# design.net
KiCad netlist of a schematic drawn in Altium Designer
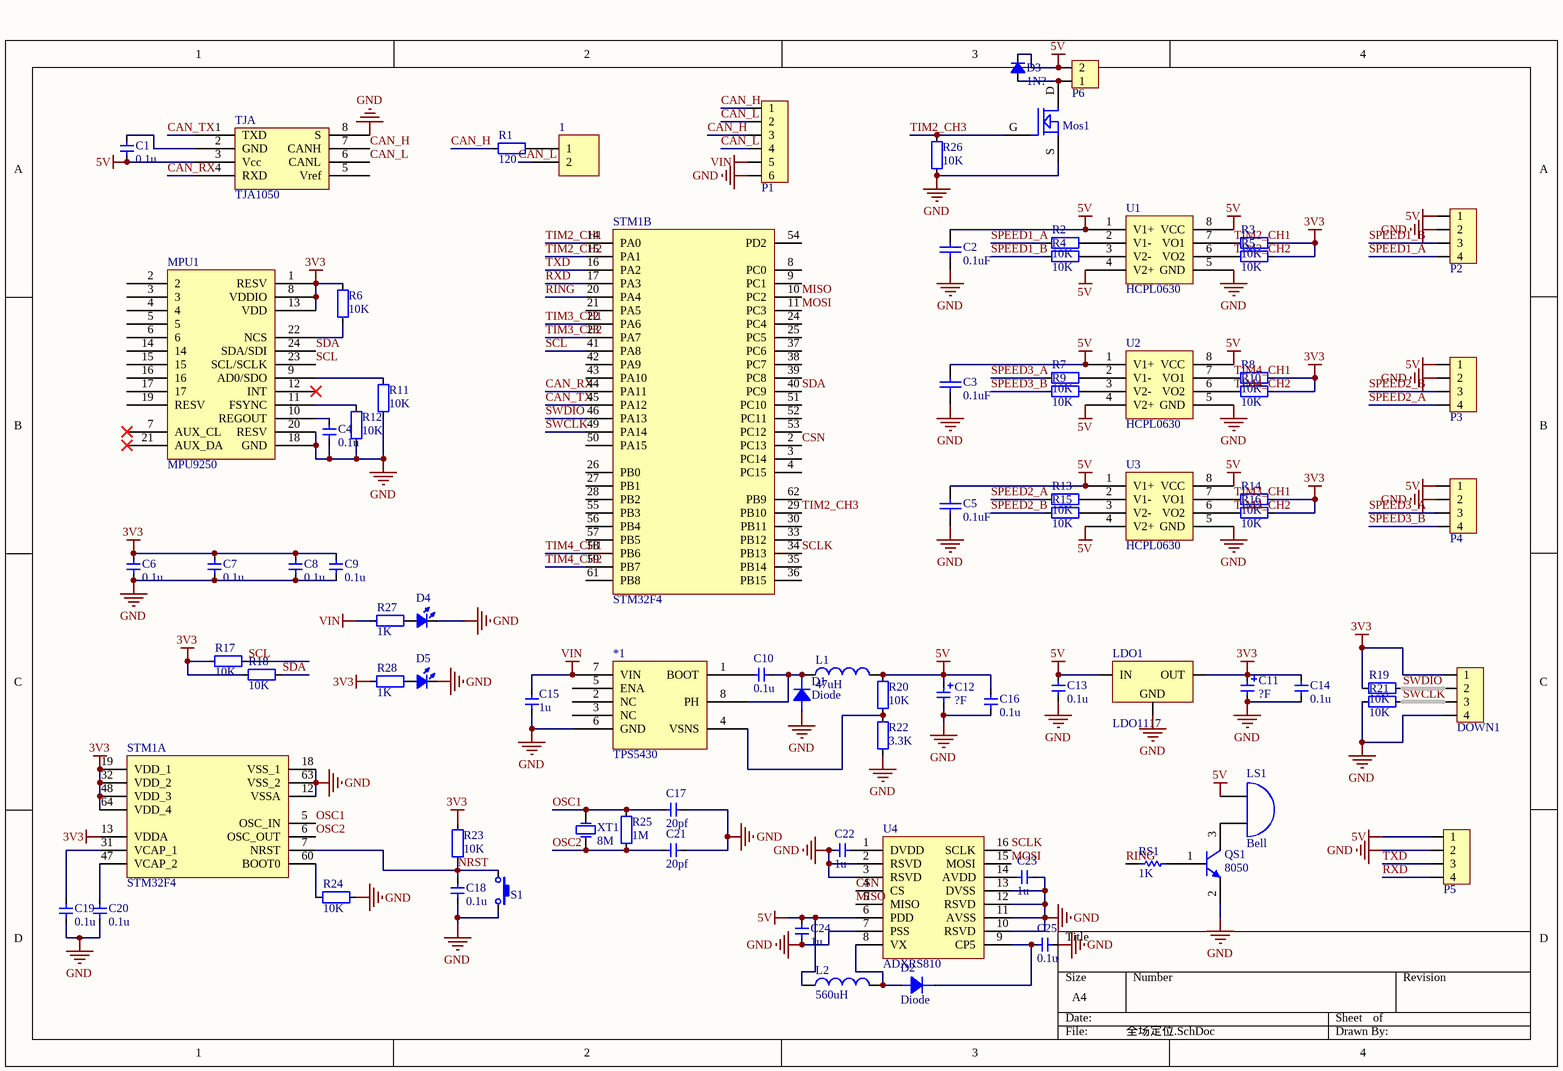
[diagram p0: 全场定位.SchDoc]

(export (version "E")
  (design (tool "Eeschema 10.0.6"))
  (components
    (comp (ref "*1")
      (value "TPS5430")
      (footprint "SOP_E150_8")
      (libsource (lib "SCH_IntegratedCircuit") (part "TPS5430"))
    )
    (comp (ref "1")
      (value "Header 2")
      (footprint "SIP2")
      (description "Header, 2-Pin")
      (fields (field (name "PUBLISHER") "Altium Limited"))
      (libsource (lib "Libraries_2014_0618") (part "Header 2"))
    )
    (comp (ref "C1")
      (value "0.1u")
      (footprint "PCB_PassiveCap:CAP_0603")
      (description "Capacitor")
      (fields (field (name "Comment") "Cap_0603"))
      (libsource (lib "SCH_Passive") (part "Cap_0603"))
    )
    (comp (ref "C2")
      (value "0.1uF")
      (footprint "CAP-MLCC-0603")
      (description "Capacitor")
      (fields (field (name "Comment") "Cap") (field (name "PUBLISHER") "Altium Limited"))
      (libsource (lib "K60-mainboard-v3.1") (part "Cap"))
    )
    (comp (ref "C3")
      (value "0.1uF")
      (footprint "CAP-MLCC-0603")
      (description "Capacitor")
      (fields (field (name "Comment") "Cap") (field (name "PUBLISHER") "Altium Limited"))
      (libsource (lib "K60-mainboard-v3.1") (part "Cap"))
    )
    (comp (ref "C4")
      (value "0.1u")
      (footprint "PCB_PassiveCap:CAP_0603")
      (description "Capacitor")
      (fields (field (name "Comment") "Cap_0603"))
      (libsource (lib "SCH_Passive") (part "Cap_0603"))
    )
    (comp (ref "C5")
      (value "0.1uF")
      (footprint "CAP-MLCC-0603")
      (description "Capacitor")
      (fields (field (name "Comment") "Cap") (field (name "PUBLISHER") "Altium Limited"))
      (libsource (lib "K60-mainboard-v3.1") (part "Cap"))
    )
    (comp (ref "C6")
      (value "0.1u")
      (footprint "PCB_PassiveCap:CAP_0603")
      (description "Capacitor")
      (fields (field (name "Comment") "Cap_0603"))
      (libsource (lib "SCH_Passive") (part "Cap_0603"))
    )
    (comp (ref "C7")
      (value "0.1u")
      (footprint "PCB_PassiveCap:CAP_0603")
      (description "Capacitor")
      (fields (field (name "Comment") "Cap_0603"))
      (libsource (lib "SCH_Passive") (part "Cap_0603"))
    )
    (comp (ref "C8")
      (value "0.1u")
      (footprint "PCB_PassiveCap:CAP_0603")
      (description "Capacitor")
      (fields (field (name "Comment") "Cap_0603"))
      (libsource (lib "SCH_Passive") (part "Cap_0603"))
    )
    (comp (ref "C9")
      (value "0.1u")
      (footprint "PCB_PassiveCap:CAP_0603")
      (description "Capacitor")
      (fields (field (name "Comment") "Cap_0603"))
      (libsource (lib "SCH_Passive") (part "Cap_0603"))
    )
    (comp (ref "C10")
      (value "0.1u")
      (footprint "PCB_PassiveCap:CAP_0603")
      (description "Capacitor")
      (fields (field (name "Comment") "Cap_0603"))
      (libsource (lib "SCH_Passive") (part "Cap_0603"))
    )
    (comp (ref "C11")
      (value "?F")
      (footprint "PCB_PassiveCap:CAP_TAN_A1206")
      (description "Capacitor")
      (fields (field (name "Comment") "Cap_Tan_1206"))
      (libsource (lib "SCH_Passive") (part "Cap_Tan_1206"))
    )
    (comp (ref "C12")
      (value "?F")
      (footprint "PCB_PassiveCap:CAP_TAN_A1206")
      (description "Capacitor")
      (fields (field (name "Comment") "Cap_Tan_1206"))
      (libsource (lib "SCH_Passive") (part "Cap_Tan_1206"))
    )
    (comp (ref "C13")
      (value "0.1u")
      (footprint "PCB_PassiveCap:CAP_0603")
      (description "Capacitor")
      (fields (field (name "Comment") "Cap_0603"))
      (libsource (lib "SCH_Passive") (part "Cap_0603"))
    )
    (comp (ref "C14")
      (value "0.1u")
      (footprint "PCB_PassiveCap:CAP_0603")
      (description "Capacitor")
      (fields (field (name "Comment") "Cap_0603"))
      (libsource (lib "SCH_Passive") (part "Cap_0603"))
    )
    (comp (ref "C15")
      (value "1u")
      (footprint "PCB_PassiveCap:CAP_0603")
      (description "Capacitor")
      (fields (field (name "Comment") "Cap_0603"))
      (libsource (lib "SCH_Passive") (part "Cap_0603"))
    )
    (comp (ref "C16")
      (value "0.1u")
      (footprint "PCB_PassiveCap:CAP_0603")
      (description "Capacitor")
      (fields (field (name "Comment") "Cap_0603"))
      (libsource (lib "SCH_Passive") (part "Cap_0603"))
    )
    (comp (ref "C17")
      (value "20pf")
      (footprint "PCB_PassiveCap:CAP_0603")
      (description "Capacitor")
      (fields (field (name "Comment") "Cap_0603"))
      (libsource (lib "SCH_Passive") (part "Cap_0603"))
    )
    (comp (ref "C18")
      (value "0.1u")
      (footprint "PCB_PassiveCap:CAP_0603")
      (description "Capacitor")
      (fields (field (name "Comment") "Cap_0603"))
      (libsource (lib "SCH_Passive") (part "Cap_0603"))
    )
    (comp (ref "C19")
      (value "0.1u")
      (footprint "PCB_PassiveCap:CAP_0603")
      (description "Capacitor")
      (fields (field (name "Comment") "Cap_0603"))
      (libsource (lib "SCH_Passive") (part "Cap_0603"))
    )
    (comp (ref "C20")
      (value "0.1u")
      (footprint "PCB_PassiveCap:CAP_0603")
      (description "Capacitor")
      (fields (field (name "Comment") "Cap_0603"))
      (libsource (lib "SCH_Passive") (part "Cap_0603"))
    )
    (comp (ref "C21")
      (value "20pf")
      (footprint "PCB_PassiveCap:CAP_0603")
      (description "Capacitor")
      (fields (field (name "Comment") "Cap_0603"))
      (libsource (lib "SCH_Passive") (part "Cap_0603"))
    )
    (comp (ref "C22")
      (value "1u")
      (footprint "PCB_PassiveCap:CAP_0603")
      (description "Capacitor")
      (fields (field (name "Comment") "Cap_0603"))
      (libsource (lib "SCH_Passive") (part "Cap_0603"))
    )
    (comp (ref "C23")
      (value "1u")
      (footprint "PCB_PassiveCap:CAP_0603")
      (description "Capacitor")
      (fields (field (name "Comment") "Cap_0603"))
      (libsource (lib "SCH_Passive") (part "Cap_0603"))
    )
    (comp (ref "C24")
      (value "1u")
      (footprint "PCB_PassiveCap:CAP_0603")
      (description "Capacitor")
      (fields (field (name "Comment") "Cap_0603"))
      (libsource (lib "SCH_Passive") (part "Cap_0603"))
    )
    (comp (ref "C25")
      (value "0.1u")
      (footprint "PCB_PassiveCap:CAP_0603")
      (description "Capacitor")
      (fields (field (name "Comment") "Cap_0603"))
      (libsource (lib "SCH_Passive") (part "Cap_0603"))
    )
    (comp (ref "D1") (value "Diode") (footprint "SS34") (libsource (lib "K60-mainboard-v3.1") (part "Diode")))
    (comp (ref "D2") (value "Diode") (footprint "SS34") (libsource (lib "K60-mainboard-v3.1") (part "Diode")))
    (comp (ref "D3")
      (value "1N?")
      (footprint "PCB_ActiveDIO:DO-214AC")
      (description "Diode")
      (fields (field (name "Comment") "Diode_SMA"))
      (libsource (lib "SCH_Active") (part "Diode_SMA"))
    )
    (comp (ref "D4")
      (value "LED_0805")
      (footprint "PCB_ActiveLED:LED_0805_YELLOW")
      (description "LED")
      (libsource (lib "SCH_Active") (part "LED_0805"))
    )
    (comp (ref "D5")
      (value "LED_0805")
      (footprint "PCB_ActiveLED:LED_0805_YELLOW")
      (description "LED")
      (libsource (lib "SCH_Active") (part "LED_0805"))
    )
    (comp (ref "DOWN1")
      (value "HDR1x4_2.54")
      (footprint "PCB_ConnectorHDR:HDR1X4_2.54_180")
      (description "Header")
      (libsource (lib "SCH_ConnectorHDR") (part "HDR1x4_2.54"))
    )
    (comp (ref "L1")
      (value "47uH")
      (footprint "CD74")
      (description "Inductor")
      (fields (field (name "PUBLISHER") "Altium Limited"))
      (libsource (lib "smartcar_example") (part "Inductor"))
    )
    (comp (ref "L2")
      (value "560uH")
      (footprint "CD74")
      (description "Inductor")
      (fields (field (name "PUBLISHER") "Altium Limited"))
      (libsource (lib "smartcar_example") (part "Inductor"))
    )
    (comp (ref "LDO1")
      (value "LDO1117")
      (footprint "PCB_IntegratedCircuit:SOT223-3")
      (description "Power")
      (libsource (lib "SCH_IntegratedCircuit") (part "LDO1117"))
    )
    (comp (ref "LS1")
      (value "Bell")
      (footprint "Ring")
      (description "Electrical Bell")
      (fields (field (name "PUBLISHER") "Altium Limited"))
      (libsource (lib "附加元件") (part "Bell"))
    )
    (comp (ref "Mos1")
      (value "MOSFET N")
      (footprint "Nmos_SOT23")
      (description "MOS SOT23")
      (libsource (lib "SCH_Active") (part "MOSFET N"))
    )
    (comp (ref "MPU1")
      (value "MPU9250")
      (footprint "QFN_P0.4_24")
      (libsource (lib "K60-mainboard-v3.1") (part "MPU9250"))
    )
    (comp (ref "P1")
      (value "HDR1x6_2.54")
      (footprint "green_6p")
      (description "Header")
      (libsource (lib "SCH_ConnectorHDR") (part "HDR1x6_2.54"))
    )
    (comp (ref "P2")
      (value "HDR1x4_2.54")
      (footprint "Libraries_2014_0618:Green_4P")
      (description "Header")
      (libsource (lib "SCH_ConnectorHDR") (part "HDR1x4_2.54"))
    )
    (comp (ref "P3")
      (value "HDR1x4_2.54")
      (footprint "green_4p")
      (description "Header")
      (libsource (lib "SCH_ConnectorHDR") (part "HDR1x4_2.54"))
    )
    (comp (ref "P4")
      (value "HDR1x4_2.54")
      (footprint "green_4p")
      (description "Header")
      (libsource (lib "SCH_ConnectorHDR") (part "HDR1x4_2.54"))
    )
    (comp (ref "P5")
      (value "HDR1x4_2.54")
      (footprint "PCB_ConnectorHDR:HDR1X4_2.54_180")
      (description "Header")
      (libsource (lib "SCH_ConnectorHDR") (part "HDR1x4_2.54"))
    )
    (comp (ref "P6") (value "Connector") (footprint "Green 2P") (libsource (lib "SCH_Connector") (part "2P")))
    (comp (ref "QS1")
      (value "8050")
      (footprint "SOT-23B_N")
      (description "NPN Bipolar Transistor")
      (fields (field (name "PUBLISHER") "Altium Limited"))
      (libsource (lib "附加元件") (part "QNPN"))
    )
    (comp (ref "R1")
      (value "120")
      (footprint "PCB_PassiveRes:RES_0603")
      (description "Resistor")
      (fields (field (name "Comment") "Res_0603"))
      (libsource (lib "SCH_Passive") (part "Res_0603"))
    )
    (comp (ref "R2")
      (value "10K")
      (footprint "PCB_PassiveRes:RES_0603")
      (description "Resistor")
      (fields (field (name "Comment") "Res_0603"))
      (libsource (lib "") (part "Res_0603_2"))
    )
    (comp (ref "R3")
      (value "10K")
      (footprint "PCB_PassiveRes:RES_0603")
      (description "Resistor")
      (fields (field (name "Comment") "Res_0603"))
      (libsource (lib "") (part "Res_0603_2"))
    )
    (comp (ref "R4")
      (value "10K")
      (footprint "PCB_PassiveRes:RES_0603")
      (description "Resistor")
      (fields (field (name "Comment") "Res_0603"))
      (libsource (lib "") (part "Res_0603_2"))
    )
    (comp (ref "R5")
      (value "10K")
      (footprint "PCB_PassiveRes:RES_0603")
      (description "Resistor")
      (fields (field (name "Comment") "Res_0603"))
      (libsource (lib "") (part "Res_0603_2"))
    )
    (comp (ref "R6")
      (value "10K")
      (footprint "PCB_PassiveRes:RES_0603")
      (description "Resistor")
      (fields (field (name "Comment") "Res_0603"))
      (libsource (lib "") (part "Res_0603_1"))
    )
    (comp (ref "R7")
      (value "10K")
      (footprint "PCB_PassiveRes:RES_0603")
      (description "Resistor")
      (fields (field (name "Comment") "Res_0603"))
      (libsource (lib "") (part "Res_0603_2"))
    )
    (comp (ref "R8")
      (value "10K")
      (footprint "PCB_PassiveRes:RES_0603")
      (description "Resistor")
      (fields (field (name "Comment") "Res_0603"))
      (libsource (lib "") (part "Res_0603_2"))
    )
    (comp (ref "R9")
      (value "10K")
      (footprint "PCB_PassiveRes:RES_0603")
      (description "Resistor")
      (fields (field (name "Comment") "Res_0603"))
      (libsource (lib "") (part "Res_0603_2"))
    )
    (comp (ref "R10")
      (value "10K")
      (footprint "PCB_PassiveRes:RES_0603")
      (description "Resistor")
      (fields (field (name "Comment") "Res_0603"))
      (libsource (lib "") (part "Res_0603_2"))
    )
    (comp (ref "R11")
      (value "10K")
      (footprint "PCB_PassiveRes:RES_0603")
      (description "Resistor")
      (fields (field (name "Comment") "Res_0603"))
      (libsource (lib "") (part "Res_0603_1"))
    )
    (comp (ref "R12")
      (value "10K")
      (footprint "PCB_PassiveRes:RES_0603")
      (description "Resistor")
      (fields (field (name "Comment") "Res_0603"))
      (libsource (lib "") (part "Res_0603_1"))
    )
    (comp (ref "R13")
      (value "10K")
      (footprint "PCB_PassiveRes:RES_0603")
      (description "Resistor")
      (fields (field (name "Comment") "Res_0603"))
      (libsource (lib "") (part "Res_0603_2"))
    )
    (comp (ref "R14")
      (value "10K")
      (footprint "PCB_PassiveRes:RES_0603")
      (description "Resistor")
      (fields (field (name "Comment") "Res_0603"))
      (libsource (lib "") (part "Res_0603_2"))
    )
    (comp (ref "R15")
      (value "10K")
      (footprint "PCB_PassiveRes:RES_0603")
      (description "Resistor")
      (fields (field (name "Comment") "Res_0603"))
      (libsource (lib "") (part "Res_0603_2"))
    )
    (comp (ref "R16")
      (value "10K")
      (footprint "PCB_PassiveRes:RES_0603")
      (description "Resistor")
      (fields (field (name "Comment") "Res_0603"))
      (libsource (lib "") (part "Res_0603_2"))
    )
    (comp (ref "R17")
      (value "10K")
      (footprint "PCB_PassiveRes:RES_0603")
      (description "Resistor")
      (fields (field (name "Comment") "Res_0603"))
      (libsource (lib "") (part "Res_0603_2"))
    )
    (comp (ref "R18")
      (value "10K")
      (footprint "PCB_PassiveRes:RES_0603")
      (description "Resistor")
      (fields (field (name "Comment") "Res_0603"))
      (libsource (lib "") (part "Res_0603_2"))
    )
    (comp (ref "R19")
      (value "10K")
      (footprint "PCB_PassiveRes:RES_0603")
      (description "Resistor")
      (fields (field (name "Comment") "Res_0603"))
      (libsource (lib "") (part "Res_0603_2"))
    )
    (comp (ref "R20")
      (value "10K")
      (footprint "PCB_PassiveRes:RES_0603")
      (description "Resistor")
      (fields (field (name "Comment") "Res_0603"))
      (libsource (lib "") (part "Res_0603_1"))
    )
    (comp (ref "R21")
      (value "10K")
      (footprint "PCB_PassiveRes:RES_0603")
      (description "Resistor")
      (fields (field (name "Comment") "Res_0603"))
      (libsource (lib "") (part "Res_0603_2"))
    )
    (comp (ref "R22")
      (value "3.3K")
      (footprint "PCB_PassiveRes:RES_0603")
      (description "Resistor")
      (fields (field (name "Comment") "Res_0603"))
      (libsource (lib "") (part "Res_0603_1"))
    )
    (comp (ref "R23")
      (value "10K")
      (footprint "PCB_PassiveRes:RES_0603")
      (description "Resistor")
      (fields (field (name "Comment") "Res_0603"))
      (libsource (lib "") (part "Res_0603_1"))
    )
    (comp (ref "R24")
      (value "10K")
      (footprint "PCB_PassiveRes:RES_0603")
      (description "Resistor")
      (fields (field (name "Comment") "Res_0603"))
      (libsource (lib "SCH_Passive") (part "Res_0603"))
    )
    (comp (ref "R25")
      (value "1M")
      (footprint "PCB_PassiveRes:RES_0603")
      (description "Resistor")
      (fields (field (name "Comment") "Res_0603"))
      (libsource (lib "") (part "Res_0603_3"))
    )
    (comp (ref "R26")
      (value "10K")
      (footprint "PCB_PassiveRes:RES_0603")
      (description "Resistor")
      (fields (field (name "Comment") "Res_0603"))
      (libsource (lib "") (part "Res_0603_1"))
    )
    (comp (ref "R27")
      (value "1K")
      (footprint "PCB_PassiveRes:RES_0603")
      (description "Resistor")
      (fields (field (name "Comment") "Res_0603"))
      (libsource (lib "SCH_Passive") (part "Res_0603"))
    )
    (comp (ref "R28")
      (value "1K")
      (footprint "PCB_PassiveRes:RES_0603")
      (description "Resistor")
      (fields (field (name "Comment") "Res_0603"))
      (libsource (lib "SCH_Passive") (part "Res_0603"))
    )
    (comp (ref "RS1")
      (value "1K")
      (footprint "RES-0603")
      (description "Resistor")
      (fields (field (name "Comment") "Res1") (field (name "PUBLISHER") "Altium Limited"))
      (libsource (lib "K60-mainboard-v3.1") (part "Res1"))
    )
    (comp (ref "S1")
      (value "ButtonTACT_3x4x2_180")
      (footprint "PCB_Switch:ButtonTACT_3x4x2_180H")
      (description "Button")
      (libsource (lib "SCH_Switch") (part "ButtonTACT_3x4x2_180"))
    )
    (comp (ref "STM1")
      (value "STM32F4")
      (footprint "PCB_IntegratedCircuit:LQFP_P0.5_64")
      (description "MCU")
      (libsource (lib "SCH_IntegratedCircuit") (part "STM32F405R"))
    )
    (comp (ref "TJA")
      (value "TJA1050")
      (footprint "SOP_E150_8")
      (libsource (lib "SCH_IntegratedCircuit") (part "TJA1050"))
    )
    (comp (ref "U1")
      (value "HCPL0630")
      (footprint "SOP_E150_8")
      (libsource (lib "SCH_IntegratedCircuit") (part "HCPL0630"))
    )
    (comp (ref "U2")
      (value "HCPL0630")
      (footprint "SOP_E150_8")
      (libsource (lib "SCH_IntegratedCircuit") (part "HCPL0630"))
    )
    (comp (ref "U3")
      (value "HCPL0630")
      (footprint "SOP_E150_8")
      (libsource (lib "SCH_IntegratedCircuit") (part "HCPL0630"))
    )
    (comp (ref "U4")
      (value "ADXRS810")
      (footprint "sop16")
      (libsource (lib "SCH_IntegratedCircuit") (part "ADXRS810"))
    )
    (comp (ref "XT1")
      (value "8M")
      (footprint "PCB_Oscillator:XT_5032_2")
      (description "Crystal Oscillator")
      (fields (field (name "Comment") "XTAL_5032_2P"))
      (libsource (lib "SCH_Oscillator") (part "XTAL_5032_2P"))
    )
  )
  (nets
    (net (code "1") (name "/CAN_H") (class "Default")
      (node (ref "P1") (pin "1") (pinfunction "1_1") (pintype "passive"))
      (node (ref "P1") (pin "3") (pinfunction "3_3") (pintype "passive"))
      (node (ref "R1") (pin "1") (pinfunction "1_1") (pintype "passive"))
      (node (ref "TJA") (pin "7") (pinfunction "CANH_7") (pintype "passive"))
    )
    (net (code "2") (name "/CAN_L") (class "Default")
      (node (ref "1") (pin "2") (pinfunction "2_2") (pintype "passive"))
      (node (ref "P1") (pin "2") (pinfunction "2_2") (pintype "passive"))
      (node (ref "P1") (pin "4") (pinfunction "4_4") (pintype "passive"))
      (node (ref "TJA") (pin "6") (pinfunction "CANL_6") (pintype "passive"))
    )
    (net (code "3") (name "/CAN_RX") (class "Default")
      (node (ref "STM1") (pin "44") (pinfunction "PA11_44") (pintype "passive"))
      (node (ref "TJA") (pin "4") (pinfunction "RXD_4") (pintype "passive"))
    )
    (net (code "4") (name "/CAN_TX") (class "Default")
      (node (ref "STM1") (pin "45") (pinfunction "PA12_45") (pintype "passive"))
      (node (ref "TJA") (pin "1") (pinfunction "TXD_1") (pintype "passive"))
    )
    (net (code "5") (name "/CSN") (class "Default")
      (node (ref "STM1") (pin "2") (pinfunction "PC13_2") (pintype "passive"))
      (node (ref "U4") (pin "4") (pinfunction "CS_4") (pintype "passive"))
    )
    (net (code "6") (name "/MISO") (class "Default")
      (node (ref "STM1") (pin "10") (pinfunction "PC2_10") (pintype "passive"))
      (node (ref "U4") (pin "5") (pinfunction "MISO_5") (pintype "passive"))
    )
    (net (code "7") (name "/MOSI") (class "Default")
      (node (ref "STM1") (pin "11") (pinfunction "PC3_11") (pintype "passive"))
      (node (ref "U4") (pin "15") (pinfunction "MOSI_15") (pintype "passive"))
    )
    (net (code "8") (name "/NRST") (class "Default")
      (node (ref "C18") (pin "2") (pinfunction "2_2") (pintype "passive"))
      (node (ref "R23") (pin "2") (pinfunction "2_2") (pintype "passive"))
      (node (ref "S1") (pin "1") (pinfunction "1_1") (pintype "passive"))
      (node (ref "STM1") (pin "7") (pinfunction "NRST_7") (pintype "passive"))
    )
    (net (code "9") (name "/OSC1") (class "Default")
      (node (ref "C17") (pin "2") (pinfunction "2_2") (pintype "passive"))
      (node (ref "R25") (pin "2") (pinfunction "2_2") (pintype "passive"))
      (node (ref "STM1") (pin "5") (pinfunction "OSC_IN_5") (pintype "passive"))
      (node (ref "XT1") (pin "2") (pinfunction "OSC2_2") (pintype "passive"))
    )
    (net (code "10") (name "/OSC2") (class "Default")
      (node (ref "C21") (pin "2") (pinfunction "2_2") (pintype "passive"))
      (node (ref "R25") (pin "1") (pinfunction "1_1") (pintype "passive"))
      (node (ref "STM1") (pin "6") (pinfunction "OSC_OUT_6") (pintype "passive"))
      (node (ref "XT1") (pin "1") (pinfunction "OSC1_1") (pintype "passive"))
    )
    (net (code "11") (name "/RING") (class "Default")
      (node (ref "RS1") (pin "2") (pinfunction "2_2") (pintype "passive"))
      (node (ref "STM1") (pin "20") (pinfunction "PA4_20") (pintype "passive"))
    )
    (net (code "12") (name "/RXD") (class "Default")
      (node (ref "P5") (pin "4") (pinfunction "4_4") (pintype "passive"))
      (node (ref "STM1") (pin "17") (pinfunction "PA3_17") (pintype "passive"))
    )
    (net (code "13") (name "/SCL") (class "Default")
      (node (ref "MPU1") (pin "23") (pinfunction "SCL/SCLK_23") (pintype "passive"))
      (node (ref "R17") (pin "1") (pinfunction "1_1") (pintype "passive"))
      (node (ref "STM1") (pin "41") (pinfunction "PA8_41") (pintype "passive"))
    )
    (net (code "14") (name "/SCLK") (class "Default")
      (node (ref "STM1") (pin "34") (pinfunction "PB13_34") (pintype "passive"))
      (node (ref "U4") (pin "16") (pinfunction "SCLK_16") (pintype "passive"))
    )
    (net (code "15") (name "/SDA") (class "Default")
      (node (ref "MPU1") (pin "24") (pinfunction "SDA/SDI_24") (pintype "passive"))
      (node (ref "R18") (pin "1") (pinfunction "1_1") (pintype "passive"))
      (node (ref "STM1") (pin "40") (pinfunction "PC9_40") (pintype "passive"))
    )
    (net (code "16") (name "/SPEED1_A") (class "Default")
      (node (ref "P2") (pin "4") (pinfunction "4_4") (pintype "passive"))
      (node (ref "R2") (pin "2") (pinfunction "2_2") (pintype "passive"))
    )
    (net (code "17") (name "/SPEED1_B") (class "Default")
      (node (ref "P2") (pin "3") (pinfunction "3_3") (pintype "passive"))
      (node (ref "R4") (pin "2") (pinfunction "2_2") (pintype "passive"))
    )
    (net (code "18") (name "/SPEED2_A") (class "Default")
      (node (ref "P3") (pin "4") (pinfunction "4_4") (pintype "passive"))
      (node (ref "R13") (pin "2") (pinfunction "2_2") (pintype "passive"))
    )
    (net (code "19") (name "/SPEED2_B") (class "Default")
      (node (ref "P3") (pin "3") (pinfunction "3_3") (pintype "passive"))
      (node (ref "R15") (pin "2") (pinfunction "2_2") (pintype "passive"))
    )
    (net (code "20") (name "/SPEED3_A") (class "Default")
      (node (ref "P4") (pin "3") (pinfunction "3_3") (pintype "passive"))
      (node (ref "R7") (pin "2") (pinfunction "2_2") (pintype "passive"))
    )
    (net (code "21") (name "/SPEED3_B") (class "Default")
      (node (ref "P4") (pin "4") (pinfunction "4_4") (pintype "passive"))
      (node (ref "R9") (pin "2") (pinfunction "2_2") (pintype "passive"))
    )
    (net (code "22") (name "/SWCLK") (class "Default")
      (node (ref "DOWN1") (pin "3") (pinfunction "3_3") (pintype "passive"))
      (node (ref "R21") (pin "1") (pinfunction "1_1") (pintype "passive"))
      (node (ref "STM1") (pin "49") (pinfunction "PA14_49") (pintype "passive"))
    )
    (net (code "23") (name "/SWDIO") (class "Default")
      (node (ref "DOWN1") (pin "2") (pinfunction "2_2") (pintype "passive"))
      (node (ref "R19") (pin "1") (pinfunction "1_1") (pintype "passive"))
      (node (ref "STM1") (pin "46") (pinfunction "PA13_46") (pintype "passive"))
    )
    (net (code "24") (name "/TIM2_CH1") (class "Default")
      (node (ref "R3") (pin "2") (pinfunction "2_2") (pintype "passive"))
      (node (ref "STM1") (pin "14") (pinfunction "PA0_14") (pintype "passive"))
      (node (ref "U1") (pin "7") (pinfunction "VO1_7") (pintype "passive"))
    )
    (net (code "25") (name "/TIM2_CH2") (class "Default")
      (node (ref "R5") (pin "2") (pinfunction "2_2") (pintype "passive"))
      (node (ref "STM1") (pin "15") (pinfunction "PA1_15") (pintype "passive"))
      (node (ref "U1") (pin "6") (pinfunction "VO2_6") (pintype "passive"))
    )
    (net (code "26") (name "/TIM2_CH3") (class "Default")
      (node (ref "Mos1") (pin "G") (pinfunction "G_G") (pintype "passive"))
      (node (ref "R26") (pin "1") (pinfunction "1_1") (pintype "passive"))
      (node (ref "STM1") (pin "29") (pinfunction "PB10_29") (pintype "passive"))
    )
    (net (code "27") (name "/TIM3_CH1") (class "Default")
      (node (ref "R14") (pin "2") (pinfunction "2_2") (pintype "passive"))
      (node (ref "STM1") (pin "22") (pinfunction "PA6_22") (pintype "passive"))
      (node (ref "U3") (pin "7") (pinfunction "VO1_7") (pintype "passive"))
    )
    (net (code "28") (name "/TIM3_CH2") (class "Default")
      (node (ref "R16") (pin "2") (pinfunction "2_2") (pintype "passive"))
      (node (ref "STM1") (pin "23") (pinfunction "PA7_23") (pintype "passive"))
      (node (ref "U3") (pin "6") (pinfunction "VO2_6") (pintype "passive"))
    )
    (net (code "29") (name "/TIM4_CH1") (class "Default")
      (node (ref "R8") (pin "2") (pinfunction "2_2") (pintype "passive"))
      (node (ref "STM1") (pin "58") (pinfunction "PB6_58") (pintype "passive"))
      (node (ref "U2") (pin "7") (pinfunction "VO1_7") (pintype "passive"))
    )
    (net (code "30") (name "/TIM4_CH2") (class "Default")
      (node (ref "R10") (pin "2") (pinfunction "2_2") (pintype "passive"))
      (node (ref "STM1") (pin "59") (pinfunction "PB7_59") (pintype "passive"))
      (node (ref "U2") (pin "6") (pinfunction "VO2_6") (pintype "passive"))
    )
    (net (code "31") (name "/TXD") (class "Default")
      (node (ref "P5") (pin "3") (pinfunction "3_3") (pintype "passive"))
      (node (ref "STM1") (pin "16") (pinfunction "PA2_16") (pintype "passive"))
    )
    (net (code "32") (name "3V3") (class "Default")
      (node (ref "C11") (pin "1") (pinfunction "1_1") (pintype "passive"))
      (node (ref "C14") (pin "1") (pinfunction "1_1") (pintype "passive"))
      (node (ref "C6") (pin "2") (pinfunction "2_2") (pintype "passive"))
      (node (ref "C7") (pin "2") (pinfunction "2_2") (pintype "passive"))
      (node (ref "C8") (pin "2") (pinfunction "2_2") (pintype "passive"))
      (node (ref "C9") (pin "2") (pinfunction "2_2") (pintype "passive"))
      (node (ref "DOWN1") (pin "1") (pinfunction "1_1") (pintype "passive"))
      (node (ref "LDO1") (pin "2") (pinfunction "OUT_2") (pintype "power_in"))
      (node (ref "MPU1") (pin "1") (pinfunction "RESV_1") (pintype "passive"))
      (node (ref "MPU1") (pin "13") (pinfunction "VDD_13") (pintype "passive"))
      (node (ref "MPU1") (pin "8") (pinfunction "VDDIO_8") (pintype "passive"))
      (node (ref "R10") (pin "1") (pinfunction "1_1") (pintype "passive"))
      (node (ref "R14") (pin "1") (pinfunction "1_1") (pintype "passive"))
      (node (ref "R16") (pin "1") (pinfunction "1_1") (pintype "passive"))
      (node (ref "R17") (pin "2") (pinfunction "2_2") (pintype "passive"))
      (node (ref "R18") (pin "2") (pinfunction "2_2") (pintype "passive"))
      (node (ref "R19") (pin "2") (pinfunction "2_2") (pintype "passive"))
      (node (ref "R23") (pin "1") (pinfunction "1_1") (pintype "passive"))
      (node (ref "R28") (pin "1") (pinfunction "1_1") (pintype "passive"))
      (node (ref "R3") (pin "1") (pinfunction "1_1") (pintype "passive"))
      (node (ref "R5") (pin "1") (pinfunction "1_1") (pintype "passive"))
      (node (ref "R6") (pin "1") (pinfunction "1_1") (pintype "passive"))
      (node (ref "R8") (pin "1") (pinfunction "1_1") (pintype "passive"))
      (node (ref "STM1") (pin "13") (pinfunction "VDDA_13") (pintype "passive"))
      (node (ref "STM1") (pin "19") (pinfunction "VDD_1_19") (pintype "passive"))
      (node (ref "STM1") (pin "32") (pinfunction "VDD_2_32") (pintype "passive"))
      (node (ref "STM1") (pin "48") (pinfunction "VDD_3_48") (pintype "passive"))
      (node (ref "STM1") (pin "64") (pinfunction "VDD_4_64") (pintype "passive"))
    )
    (net (code "33") (name "5V") (class "Default")
      (node (ref "C1") (pin "1") (pinfunction "1_1") (pintype "passive"))
      (node (ref "C12") (pin "1") (pinfunction "1_1") (pintype "passive"))
      (node (ref "C13") (pin "1") (pinfunction "1_1") (pintype "passive"))
      (node (ref "C16") (pin "1") (pinfunction "1_1") (pintype "passive"))
      (node (ref "C2") (pin "1") (pinfunction "1_1") (pintype "passive"))
      (node (ref "C24") (pin "1") (pinfunction "1_1") (pintype "passive"))
      (node (ref "C3") (pin "1") (pinfunction "1_1") (pintype "passive"))
      (node (ref "C5") (pin "1") (pinfunction "1_1") (pintype "passive"))
      (node (ref "D3") (pin "2") (pinfunction "K_2") (pintype "passive"))
      (node (ref "L1") (pin "2") (pinfunction "2_2") (pintype "passive"))
      (node (ref "L2") (pin "1") (pinfunction "1_1") (pintype "passive"))
      (node (ref "LDO1") (pin "3") (pinfunction "IN_3") (pintype "power_in"))
      (node (ref "LS1") (pin "1") (pinfunction "A_1") (pintype "passive"))
      (node (ref "P2") (pin "1") (pinfunction "1_1") (pintype "passive"))
      (node (ref "P3") (pin "1") (pinfunction "1_1") (pintype "passive"))
      (node (ref "P4") (pin "1") (pinfunction "1_1") (pintype "passive"))
      (node (ref "P5") (pin "1") (pinfunction "1_1") (pintype "passive"))
      (node (ref "P6") (pin "2") (pinfunction "2_2") (pintype "passive"))
      (node (ref "R20") (pin "1") (pinfunction "1_1") (pintype "passive"))
      (node (ref "TJA") (pin "3") (pinfunction "Vcc_3") (pintype "passive"))
      (node (ref "U1") (pin "1") (pinfunction "V1+_1") (pintype "passive"))
      (node (ref "U1") (pin "4") (pinfunction "V2+_4") (pintype "passive"))
      (node (ref "U1") (pin "8") (pinfunction "VCC_8") (pintype "passive"))
      (node (ref "U2") (pin "1") (pinfunction "V1+_1") (pintype "passive"))
      (node (ref "U2") (pin "4") (pinfunction "V2+_4") (pintype "passive"))
      (node (ref "U2") (pin "8") (pinfunction "VCC_8") (pintype "passive"))
      (node (ref "U3") (pin "1") (pinfunction "V1+_1") (pintype "passive"))
      (node (ref "U3") (pin "4") (pinfunction "V2+_4") (pintype "passive"))
      (node (ref "U3") (pin "8") (pinfunction "VCC_8") (pintype "passive"))
      (node (ref "U4") (pin "6") (pinfunction "PDD_6") (pintype "passive"))
    )
    (net (code "34") (name "GND") (class "Default")
      (node (ref "*1") (pin "6") (pinfunction "GND_6") (pintype "passive"))
      (node (ref "C11") (pin "2") (pinfunction "2_2") (pintype "passive"))
      (node (ref "C12") (pin "2") (pinfunction "2_2") (pintype "passive"))
      (node (ref "C13") (pin "2") (pinfunction "2_2") (pintype "passive"))
      (node (ref "C14") (pin "2") (pinfunction "2_2") (pintype "passive"))
      (node (ref "C15") (pin "1") (pinfunction "1_1") (pintype "passive"))
      (node (ref "C16") (pin "2") (pinfunction "2_2") (pintype "passive"))
      (node (ref "C17") (pin "1") (pinfunction "1_1") (pintype "passive"))
      (node (ref "C18") (pin "1") (pinfunction "1_1") (pintype "passive"))
      (node (ref "C19") (pin "2") (pinfunction "2_2") (pintype "passive"))
      (node (ref "C2") (pin "2") (pinfunction "2_2") (pintype "passive"))
      (node (ref "C20") (pin "2") (pinfunction "2_2") (pintype "passive"))
      (node (ref "C21") (pin "1") (pinfunction "1_1") (pintype "passive"))
      (node (ref "C22") (pin "2") (pinfunction "2_2") (pintype "passive"))
      (node (ref "C23") (pin "2") (pinfunction "2_2") (pintype "passive"))
      (node (ref "C24") (pin "2") (pinfunction "2_2") (pintype "passive"))
      (node (ref "C25") (pin "1") (pinfunction "1_1") (pintype "passive"))
      (node (ref "C3") (pin "2") (pinfunction "2_2") (pintype "passive"))
      (node (ref "C4") (pin "2") (pinfunction "2_2") (pintype "passive"))
      (node (ref "C5") (pin "2") (pinfunction "2_2") (pintype "passive"))
      (node (ref "C6") (pin "1") (pinfunction "1_1") (pintype "passive"))
      (node (ref "C7") (pin "1") (pinfunction "1_1") (pintype "passive"))
      (node (ref "C8") (pin "1") (pinfunction "1_1") (pintype "passive"))
      (node (ref "C9") (pin "1") (pinfunction "1_1") (pintype "passive"))
      (node (ref "D1") (pin "A") (pinfunction "1_A") (pintype "passive"))
      (node (ref "D4") (pin "2") (pinfunction "K_2") (pintype "passive"))
      (node (ref "D5") (pin "2") (pinfunction "K_2") (pintype "passive"))
      (node (ref "DOWN1") (pin "4") (pinfunction "4_4") (pintype "passive"))
      (node (ref "LDO1") (pin "1") (pinfunction "GND_1") (pintype "power_in"))
      (node (ref "MPU1") (pin "18") (pinfunction "GND_18") (pintype "passive"))
      (node (ref "MPU1") (pin "20") (pinfunction "RESV_20") (pintype "passive"))
      (node (ref "Mos1") (pin "S") (pinfunction "S_S") (pintype "passive"))
      (node (ref "P1") (pin "6") (pinfunction "6_6") (pintype "passive"))
      (node (ref "P2") (pin "2") (pinfunction "2_2") (pintype "passive"))
      (node (ref "P3") (pin "2") (pinfunction "2_2") (pintype "passive"))
      (node (ref "P4") (pin "2") (pinfunction "2_2") (pintype "passive"))
      (node (ref "P5") (pin "2") (pinfunction "2_2") (pintype "passive"))
      (node (ref "QS1") (pin "2") (pinfunction "E_2") (pintype "passive"))
      (node (ref "R11") (pin "2") (pinfunction "2_2") (pintype "passive"))
      (node (ref "R12") (pin "2") (pinfunction "2_2") (pintype "passive"))
      (node (ref "R21") (pin "2") (pinfunction "2_2") (pintype "passive"))
      (node (ref "R22") (pin "2") (pinfunction "2_2") (pintype "passive"))
      (node (ref "R24") (pin "2") (pinfunction "2_2") (pintype "passive"))
      (node (ref "R26") (pin "2") (pinfunction "2_2") (pintype "passive"))
      (node (ref "S1") (pin "2") (pinfunction "2_2") (pintype "passive"))
      (node (ref "STM1") (pin "12") (pinfunction "VSSA_12") (pintype "passive"))
      (node (ref "STM1") (pin "18") (pinfunction "VSS_1_18") (pintype "passive"))
      (node (ref "STM1") (pin "63") (pinfunction "VSS_2_63") (pintype "passive"))
      (node (ref "TJA") (pin "8") (pinfunction "S_8") (pintype "passive"))
      (node (ref "U1") (pin "5") (pinfunction "GND_5") (pintype "passive"))
      (node (ref "U2") (pin "5") (pinfunction "GND_5") (pintype "passive"))
      (node (ref "U3") (pin "5") (pinfunction "GND_5") (pintype "passive"))
      (node (ref "U4") (pin "10") (pinfunction "RSVD_10") (pintype "passive"))
      (node (ref "U4") (pin "11") (pinfunction "AVSS_11") (pintype "passive"))
      (node (ref "U4") (pin "12") (pinfunction "RSVD_12") (pintype "passive"))
      (node (ref "U4") (pin "13") (pinfunction "DVSS_13") (pintype "passive"))
      (node (ref "U4") (pin "2") (pinfunction "RSVD_2") (pintype "passive"))
      (node (ref "U4") (pin "3") (pinfunction "RSVD_3") (pintype "passive"))
      (node (ref "U4") (pin "7") (pinfunction "PSS_7") (pintype "passive"))
    )
    (net (code "35") (name "Net-(*1-BOOT)") (class "Default")
      (node (ref "*1") (pin "1") (pinfunction "BOOT_1") (pintype "passive"))
      (node (ref "C10") (pin "2") (pinfunction "2_2") (pintype "passive"))
    )
    (net (code "36") (name "Net-(*1-PH)") (class "Default")
      (node (ref "*1") (pin "8") (pinfunction "PH_8") (pintype "passive"))
      (node (ref "C10") (pin "1") (pinfunction "1_1") (pintype "passive"))
      (node (ref "D1") (pin "K") (pinfunction "2_K") (pintype "passive"))
      (node (ref "L1") (pin "1") (pinfunction "1_1") (pintype "passive"))
    )
    (net (code "37") (name "Net-(*1-VSNS)") (class "Default")
      (node (ref "*1") (pin "4") (pinfunction "VSNS_4") (pintype "passive"))
      (node (ref "R20") (pin "2") (pinfunction "2_2") (pintype "passive"))
      (node (ref "R22") (pin "1") (pinfunction "1_1") (pintype "passive"))
    )
    (net (code "38") (name "Net-(1-Pad1)") (class "Default")
      (node (ref "1") (pin "1") (pinfunction "1_1") (pintype "passive"))
      (node (ref "R1") (pin "2") (pinfunction "2_2") (pintype "passive"))
    )
    (net (code "39") (name "Net-(D2-1)") (class "Default")
      (node (ref "D2") (pin "A") (pinfunction "1_A") (pintype "passive"))
      (node (ref "L2") (pin "2") (pinfunction "2_2") (pintype "passive"))
      (node (ref "U4") (pin "8") (pinfunction "VX_8") (pintype "passive"))
    )
    (net (code "40") (name "Net-(D2-2)") (class "Default")
      (node (ref "C25") (pin "2") (pinfunction "2_2") (pintype "passive"))
      (node (ref "D2") (pin "K") (pinfunction "2_K") (pintype "passive"))
      (node (ref "U4") (pin "9") (pinfunction "CP5_9") (pintype "passive"))
    )
    (net (code "41") (name "Net-(D3-A)") (class "Default")
      (node (ref "D3") (pin "1") (pinfunction "A_1") (pintype "passive"))
      (node (ref "Mos1") (pin "D") (pinfunction "D_D") (pintype "passive"))
      (node (ref "P6") (pin "1") (pinfunction "1_1") (pintype "passive"))
    )
    (net (code "42") (name "Net-(D4-A)") (class "Default")
      (node (ref "D4") (pin "1") (pinfunction "A_1") (pintype "passive"))
      (node (ref "R27") (pin "2") (pinfunction "2_2") (pintype "passive"))
    )
    (net (code "43") (name "Net-(D5-A)") (class "Default")
      (node (ref "D5") (pin "1") (pinfunction "A_1") (pintype "passive"))
      (node (ref "R28") (pin "2") (pinfunction "2_2") (pintype "passive"))
    )
    (net (code "44") (name "Net-(LS1-B)") (class "Default")
      (node (ref "LS1") (pin "2") (pinfunction "B_2") (pintype "passive"))
      (node (ref "QS1") (pin "3") (pinfunction "C_3") (pintype "passive"))
    )
    (net (code "45") (name "Net-(MPU1-AD0{slash}SDO)") (class "Default")
      (node (ref "MPU1") (pin "9") (pinfunction "AD0/SDO_9") (pintype "passive"))
      (node (ref "R11") (pin "1") (pinfunction "1_1") (pintype "passive"))
    )
    (net (code "46") (name "Net-(MPU1-FSYNC)") (class "Default")
      (node (ref "MPU1") (pin "11") (pinfunction "FSYNC_11") (pintype "passive"))
      (node (ref "R12") (pin "1") (pinfunction "1_1") (pintype "passive"))
    )
    (net (code "47") (name "Net-(MPU1-NCS)") (class "Default")
      (node (ref "MPU1") (pin "22") (pinfunction "NCS_22") (pintype "passive"))
      (node (ref "R6") (pin "2") (pinfunction "2_2") (pintype "passive"))
    )
    (net (code "48") (name "Net-(MPU1-REGOUT)") (class "Default")
      (node (ref "C4") (pin "1") (pinfunction "1_1") (pintype "passive"))
      (node (ref "MPU1") (pin "10") (pinfunction "REGOUT_10") (pintype "passive"))
    )
    (net (code "49") (name "Net-(QS1-B)") (class "Default")
      (node (ref "QS1") (pin "1") (pinfunction "B_1") (pintype "passive"))
      (node (ref "RS1") (pin "1") (pinfunction "1_1") (pintype "passive"))
    )
    (net (code "50") (name "Net-(STM1A-BOOT0)") (class "Default")
      (node (ref "R24") (pin "1") (pinfunction "1_1") (pintype "passive"))
      (node (ref "STM1") (pin "60") (pinfunction "BOOT0_60") (pintype "passive"))
    )
    (net (code "51") (name "Net-(STM1A-VCAP_1)") (class "Default")
      (node (ref "C19") (pin "1") (pinfunction "1_1") (pintype "passive"))
      (node (ref "STM1") (pin "31") (pinfunction "VCAP_1_31") (pintype "passive"))
    )
    (net (code "52") (name "Net-(STM1A-VCAP_2)") (class "Default")
      (node (ref "C20") (pin "1") (pinfunction "1_1") (pintype "passive"))
      (node (ref "STM1") (pin "47") (pinfunction "VCAP_2_47") (pintype "passive"))
    )
    (net (code "53") (name "Net-(TJA-GND)") (class "Default")
      (node (ref "C1") (pin "2") (pinfunction "2_2") (pintype "passive"))
      (node (ref "TJA") (pin "2") (pinfunction "GND_2") (pintype "passive"))
    )
    (net (code "54") (name "Net-(U1-V1-)") (class "Default")
      (node (ref "R2") (pin "1") (pinfunction "1_1") (pintype "passive"))
      (node (ref "U1") (pin "2") (pinfunction "V1-_2") (pintype "passive"))
    )
    (net (code "55") (name "Net-(U1-V2-)") (class "Default")
      (node (ref "R4") (pin "1") (pinfunction "1_1") (pintype "passive"))
      (node (ref "U1") (pin "3") (pinfunction "V2-_3") (pintype "passive"))
    )
    (net (code "56") (name "Net-(U2-V1-)") (class "Default")
      (node (ref "R7") (pin "1") (pinfunction "1_1") (pintype "passive"))
      (node (ref "U2") (pin "2") (pinfunction "V1-_2") (pintype "passive"))
    )
    (net (code "57") (name "Net-(U2-V2-)") (class "Default")
      (node (ref "R9") (pin "1") (pinfunction "1_1") (pintype "passive"))
      (node (ref "U2") (pin "3") (pinfunction "V2-_3") (pintype "passive"))
    )
    (net (code "58") (name "Net-(U3-V1-)") (class "Default")
      (node (ref "R13") (pin "1") (pinfunction "1_1") (pintype "passive"))
      (node (ref "U3") (pin "2") (pinfunction "V1-_2") (pintype "passive"))
    )
    (net (code "59") (name "Net-(U3-V2-)") (class "Default")
      (node (ref "R15") (pin "1") (pinfunction "1_1") (pintype "passive"))
      (node (ref "U3") (pin "3") (pinfunction "V2-_3") (pintype "passive"))
    )
    (net (code "60") (name "Net-(U4-AVDD)") (class "Default")
      (node (ref "C23") (pin "1") (pinfunction "1_1") (pintype "passive"))
      (node (ref "U4") (pin "14") (pinfunction "AVDD_14") (pintype "passive"))
    )
    (net (code "61") (name "Net-(U4-DVDD)") (class "Default")
      (node (ref "C22") (pin "1") (pinfunction "1_1") (pintype "passive"))
      (node (ref "U4") (pin "1") (pinfunction "DVDD_1") (pintype "passive"))
    )
    (net (code "62") (name "VIN") (class "Default")
      (node (ref "*1") (pin "7") (pinfunction "VIN_7") (pintype "passive"))
      (node (ref "C15") (pin "2") (pinfunction "2_2") (pintype "passive"))
      (node (ref "P1") (pin "5") (pinfunction "5_5") (pintype "passive"))
      (node (ref "R27") (pin "1") (pinfunction "1_1") (pintype "passive"))
    )
    (net (code "63") (name "unconnected-(*1-ENA-Pad5)") (class "Default")
      (node (ref "*1") (pin "5") (pinfunction "ENA_5") (pintype "passive"))
    )
    (net (code "64") (name "unconnected-(*1-NC-Pad2)") (class "Default")
      (node (ref "*1") (pin "2") (pinfunction "NC_2") (pintype "passive"))
    )
    (net (code "65") (name "unconnected-(*1-NC-Pad3)") (class "Default")
      (node (ref "*1") (pin "3") (pinfunction "NC_3") (pintype "passive"))
    )
    (net (code "66") (name "unconnected-(MPU1-AUX_CL-Pad7)") (class "Default")
      (node (ref "MPU1") (pin "7") (pinfunction "AUX_CL_7") (pintype "passive+no_connect"))
    )
    (net (code "67") (name "unconnected-(MPU1-AUX_DA-Pad21)") (class "Default")
      (node (ref "MPU1") (pin "21") (pinfunction "AUX_DA_21") (pintype "passive+no_connect"))
    )
    (net (code "68") (name "unconnected-(MPU1-INT-Pad12)") (class "Default")
      (node (ref "MPU1") (pin "12") (pinfunction "INT_12") (pintype "passive+no_connect"))
    )
    (net (code "69") (name "unconnected-(MPU1-Pad2)") (class "Default")
      (node (ref "MPU1") (pin "2") (pinfunction "2_2") (pintype "passive"))
    )
    (net (code "70") (name "unconnected-(MPU1-Pad3)") (class "Default")
      (node (ref "MPU1") (pin "3") (pinfunction "3_3") (pintype "passive"))
    )
    (net (code "71") (name "unconnected-(MPU1-Pad4)") (class "Default")
      (node (ref "MPU1") (pin "4") (pinfunction "4_4") (pintype "passive"))
    )
    (net (code "72") (name "unconnected-(MPU1-Pad5)") (class "Default")
      (node (ref "MPU1") (pin "5") (pinfunction "5_5") (pintype "passive"))
    )
    (net (code "73") (name "unconnected-(MPU1-Pad6)") (class "Default")
      (node (ref "MPU1") (pin "6") (pinfunction "6_6") (pintype "passive"))
    )
    (net (code "74") (name "unconnected-(MPU1-Pad14)") (class "Default")
      (node (ref "MPU1") (pin "14") (pinfunction "14_14") (pintype "passive"))
    )
    (net (code "75") (name "unconnected-(MPU1-Pad15)") (class "Default")
      (node (ref "MPU1") (pin "15") (pinfunction "15_15") (pintype "passive"))
    )
    (net (code "76") (name "unconnected-(MPU1-Pad16)") (class "Default")
      (node (ref "MPU1") (pin "16") (pinfunction "16_16") (pintype "passive"))
    )
    (net (code "77") (name "unconnected-(MPU1-Pad17)") (class "Default")
      (node (ref "MPU1") (pin "17") (pinfunction "17_17") (pintype "passive"))
    )
    (net (code "78") (name "unconnected-(MPU1-RESV-Pad19)") (class "Default")
      (node (ref "MPU1") (pin "19") (pinfunction "RESV_19") (pintype "passive"))
    )
    (net (code "79") (name "unconnected-(STM1B-PA5-Pad21)") (class "Default")
      (node (ref "STM1") (pin "21") (pinfunction "PA5_21") (pintype "passive"))
    )
    (net (code "80") (name "unconnected-(STM1B-PA9-Pad42)") (class "Default")
      (node (ref "STM1") (pin "42") (pinfunction "PA9_42") (pintype "passive"))
    )
    (net (code "81") (name "unconnected-(STM1B-PA10-Pad43)") (class "Default")
      (node (ref "STM1") (pin "43") (pinfunction "PA10_43") (pintype "passive"))
    )
    (net (code "82") (name "unconnected-(STM1B-PA15-Pad50)") (class "Default")
      (node (ref "STM1") (pin "50") (pinfunction "PA15_50") (pintype "passive"))
    )
    (net (code "83") (name "unconnected-(STM1B-PB0-Pad26)") (class "Default")
      (node (ref "STM1") (pin "26") (pinfunction "PB0_26") (pintype "passive"))
    )
    (net (code "84") (name "unconnected-(STM1B-PB1-Pad27)") (class "Default")
      (node (ref "STM1") (pin "27") (pinfunction "PB1_27") (pintype "passive"))
    )
    (net (code "85") (name "unconnected-(STM1B-PB2-Pad28)") (class "Default")
      (node (ref "STM1") (pin "28") (pinfunction "PB2_28") (pintype "passive"))
    )
    (net (code "86") (name "unconnected-(STM1B-PB3-Pad55)") (class "Default")
      (node (ref "STM1") (pin "55") (pinfunction "PB3_55") (pintype "passive"))
    )
    (net (code "87") (name "unconnected-(STM1B-PB4-Pad56)") (class "Default")
      (node (ref "STM1") (pin "56") (pinfunction "PB4_56") (pintype "passive"))
    )
    (net (code "88") (name "unconnected-(STM1B-PB5-Pad57)") (class "Default")
      (node (ref "STM1") (pin "57") (pinfunction "PB5_57") (pintype "passive"))
    )
    (net (code "89") (name "unconnected-(STM1B-PB8-Pad61)") (class "Default")
      (node (ref "STM1") (pin "61") (pinfunction "PB8_61") (pintype "passive"))
    )
    (net (code "90") (name "unconnected-(STM1B-PB9-Pad62)") (class "Default")
      (node (ref "STM1") (pin "62") (pinfunction "PB9_62") (pintype "passive"))
    )
    (net (code "91") (name "unconnected-(STM1B-PB11-Pad30)") (class "Default")
      (node (ref "STM1") (pin "30") (pinfunction "PB11_30") (pintype "passive"))
    )
    (net (code "92") (name "unconnected-(STM1B-PB12-Pad33)") (class "Default")
      (node (ref "STM1") (pin "33") (pinfunction "PB12_33") (pintype "passive"))
    )
    (net (code "93") (name "unconnected-(STM1B-PB14-Pad35)") (class "Default")
      (node (ref "STM1") (pin "35") (pinfunction "PB14_35") (pintype "passive"))
    )
    (net (code "94") (name "unconnected-(STM1B-PB15-Pad36)") (class "Default")
      (node (ref "STM1") (pin "36") (pinfunction "PB15_36") (pintype "passive"))
    )
    (net (code "95") (name "unconnected-(STM1B-PC0-Pad8)") (class "Default")
      (node (ref "STM1") (pin "8") (pinfunction "PC0_8") (pintype "passive"))
    )
    (net (code "96") (name "unconnected-(STM1B-PC1-Pad9)") (class "Default")
      (node (ref "STM1") (pin "9") (pinfunction "PC1_9") (pintype "passive"))
    )
    (net (code "97") (name "unconnected-(STM1B-PC4-Pad24)") (class "Default")
      (node (ref "STM1") (pin "24") (pinfunction "PC4_24") (pintype "passive"))
    )
    (net (code "98") (name "unconnected-(STM1B-PC5-Pad25)") (class "Default")
      (node (ref "STM1") (pin "25") (pinfunction "PC5_25") (pintype "passive"))
    )
    (net (code "99") (name "unconnected-(STM1B-PC6-Pad37)") (class "Default")
      (node (ref "STM1") (pin "37") (pinfunction "PC6_37") (pintype "passive"))
    )
    (net (code "100") (name "unconnected-(STM1B-PC7-Pad38)") (class "Default")
      (node (ref "STM1") (pin "38") (pinfunction "PC7_38") (pintype "passive"))
    )
    (net (code "101") (name "unconnected-(STM1B-PC8-Pad39)") (class "Default")
      (node (ref "STM1") (pin "39") (pinfunction "PC8_39") (pintype "passive"))
    )
    (net (code "102") (name "unconnected-(STM1B-PC10-Pad51)") (class "Default")
      (node (ref "STM1") (pin "51") (pinfunction "PC10_51") (pintype "passive"))
    )
    (net (code "103") (name "unconnected-(STM1B-PC11-Pad52)") (class "Default")
      (node (ref "STM1") (pin "52") (pinfunction "PC11_52") (pintype "passive"))
    )
    (net (code "104") (name "unconnected-(STM1B-PC12-Pad53)") (class "Default")
      (node (ref "STM1") (pin "53") (pinfunction "PC12_53") (pintype "passive"))
    )
    (net (code "105") (name "unconnected-(STM1B-PC14-Pad3)") (class "Default")
      (node (ref "STM1") (pin "3") (pinfunction "PC14_3") (pintype "passive"))
    )
    (net (code "106") (name "unconnected-(STM1B-PC15-Pad4)") (class "Default")
      (node (ref "STM1") (pin "4") (pinfunction "PC15_4") (pintype "passive"))
    )
    (net (code "107") (name "unconnected-(STM1B-PD2-Pad54)") (class "Default")
      (node (ref "STM1") (pin "54") (pinfunction "PD2_54") (pintype "passive"))
    )
    (net (code "108") (name "unconnected-(TJA-Vref-Pad5)") (class "Default")
      (node (ref "TJA") (pin "5") (pinfunction "Vref_5") (pintype "passive"))
    )
  )
)
